# stm32f103_pin1.net
KiCad netlist of a schematic drawn in EAGLE
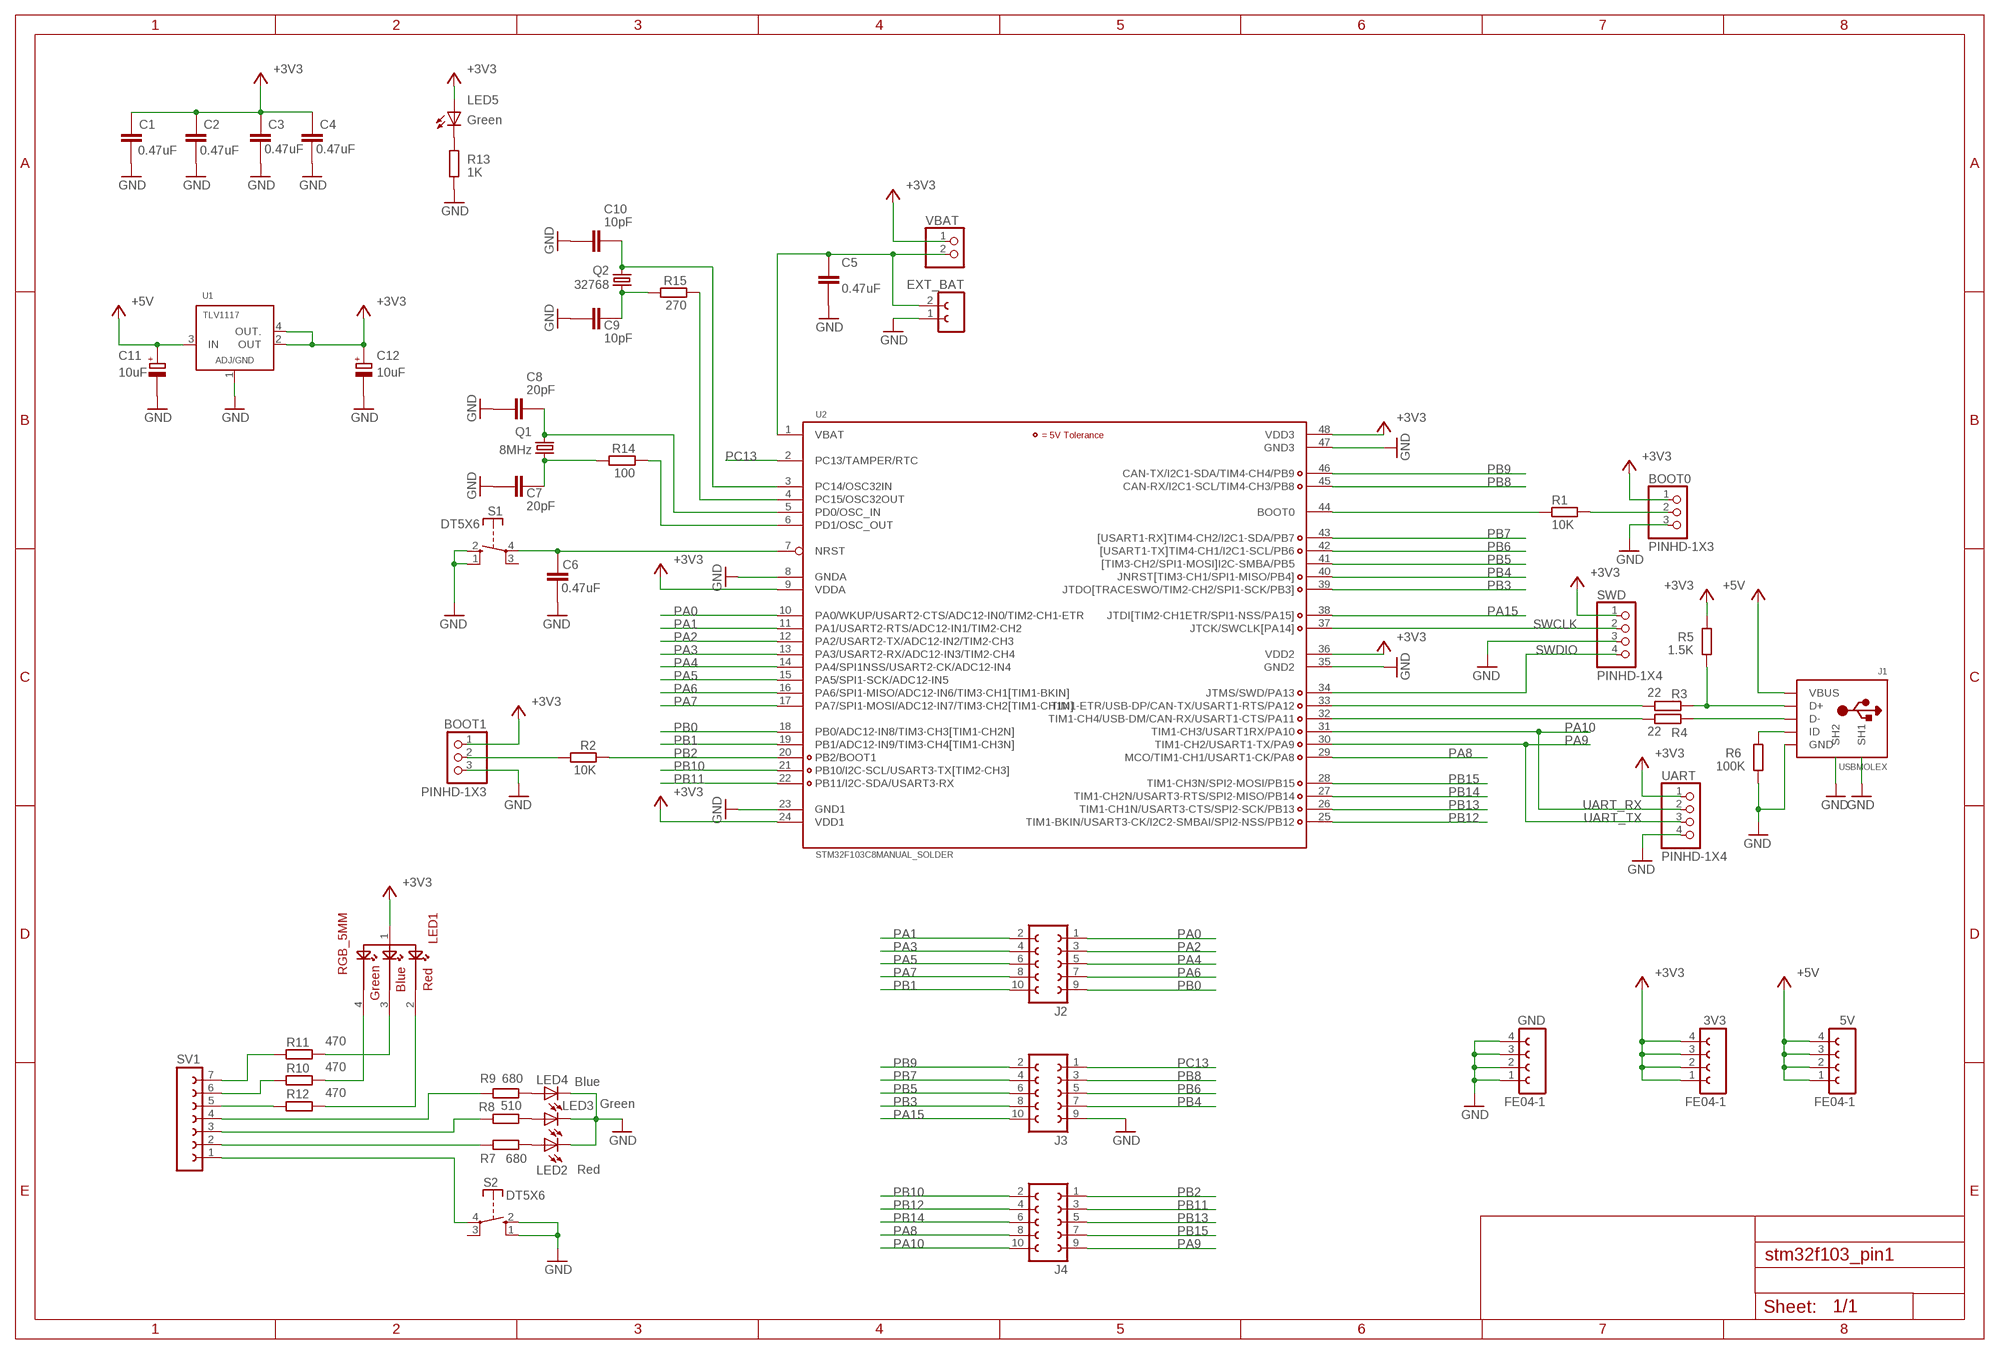
[diagram p0: schematic, sheet 1]

(export (version "E")
  (design (tool "Eeschema 10.0.6"))
  (components
    (comp (ref "3V3")
      (value "FE04-1")
      (footprint "eagle-import:FE04-1")
      (libsource (lib "eagle-import") (part "FE04-1"))
    )
    (comp (ref "5V")
      (value "FE04-1")
      (footprint "eagle-import:FE04-1")
      (libsource (lib "eagle-import") (part "FE04-1"))
    )
    (comp (ref "BOOT0")
      (value "PINHD-1X3")
      (footprint "eagle-import:1X03")
      (libsource (lib "eagle-import") (part "PINHD-1X3"))
    )
    (comp (ref "BOOT1")
      (value "PINHD-1X3")
      (footprint "eagle-import:1X03")
      (libsource (lib "eagle-import") (part "PINHD-1X3"))
    )
    (comp (ref "C1")
      (value "0.47uF")
      (footprint "eagle-import:CAPC2012X145AN")
      (libsource (lib "eagle-import") (part "CAPACITOR_0805"))
    )
    (comp (ref "C2")
      (value "0.47uF")
      (footprint "eagle-import:CAPC2012X145AN")
      (libsource (lib "eagle-import") (part "CAPACITOR_0805"))
    )
    (comp (ref "C3")
      (value "0.47uF")
      (footprint "eagle-import:CAPC2012X145AN")
      (libsource (lib "eagle-import") (part "CAPACITOR_0805"))
    )
    (comp (ref "C4")
      (value "0.47uF")
      (footprint "eagle-import:CAPC2012X145AN")
      (libsource (lib "eagle-import") (part "CAPACITOR_0805"))
    )
    (comp (ref "C5")
      (value "0.47uF")
      (footprint "eagle-import:CAPC2012X145AN")
      (libsource (lib "eagle-import") (part "CAPACITOR_0805"))
    )
    (comp (ref "C6")
      (value "0.47uF")
      (footprint "eagle-import:CAPC2012X145AN")
      (libsource (lib "eagle-import") (part "CAPACITOR_0805"))
    )
    (comp (ref "C7")
      (value "20pF")
      (footprint "eagle-import:CAPC2012X145AN")
      (libsource (lib "eagle-import") (part "CAPACITOR_0805"))
    )
    (comp (ref "C8")
      (value "20pF")
      (footprint "eagle-import:CAPC2012X145AN")
      (libsource (lib "eagle-import") (part "CAPACITOR_0805"))
    )
    (comp (ref "C9")
      (value "10pF")
      (footprint "eagle-import:CAPC2012X145AN")
      (libsource (lib "eagle-import") (part "CAPACITOR_0805"))
    )
    (comp (ref "C10")
      (value "10pF")
      (footprint "eagle-import:CAPC2012X145AN")
      (libsource (lib "eagle-import") (part "CAPACITOR_0805"))
    )
    (comp (ref "C11")
      (value "10uF")
      (footprint "eagle-import:CAPMP3216X180N")
      (libsource (lib "eagle-import") (part "POLARISED_A_CASE"))
    )
    (comp (ref "C12")
      (value "10uF")
      (footprint "eagle-import:CAPMP3216X180N")
      (libsource (lib "eagle-import") (part "POLARISED_A_CASE"))
    )
    (comp (ref "EXT_BAT")
      (value "FE02-1")
      (footprint "eagle-import:FE02-1")
      (libsource (lib "eagle-import") (part "FE02-1"))
    )
    (comp (ref "GND")
      (value "FE04-1")
      (footprint "eagle-import:FE04-1")
      (libsource (lib "eagle-import") (part "FE04-1"))
    )
    (comp (ref "J1")
      (value "USBMOLEX")
      (footprint "eagle-import:HW-MU-5F-20")
      (libsource (lib "eagle-import") (part "USBMOLEX"))
    )
    (comp (ref "J2")
      (value "FE05-2")
      (footprint "eagle-import:FE05-2")
      (fields (field (name "OC_FARNELL") "unknown") (field (name "OC_NEWARK") "unknown"))
      (libsource (lib "eagle-import") (part "FE05-2"))
    )
    (comp (ref "J3")
      (value "FE05-2")
      (footprint "eagle-import:FE05-2")
      (libsource (lib "eagle-import") (part "FE05-2"))
    )
    (comp (ref "J4")
      (value "FE05-2")
      (footprint "eagle-import:FE05-2")
      (fields (field (name "OC_FARNELL") "unknown") (field (name "OC_NEWARK") "unknown"))
      (libsource (lib "eagle-import") (part "FE05-2"))
    )
    (comp (ref "LED1")
      (value "RGB_5MM")
      (footprint "eagle-import:RGB_5MM")
      (libsource (lib "eagle-import") (part "RGB_5MM"))
    )
    (comp (ref "LED2")
      (value "Red")
      (footprint "eagle-import:CHIP-LED0805")
      (libsource (lib "eagle-import") (part "LEDCHIP-LED0805"))
    )
    (comp (ref "LED3")
      (value "Green")
      (footprint "eagle-import:CHIP-LED0805")
      (libsource (lib "eagle-import") (part "LEDCHIP-LED0805"))
    )
    (comp (ref "LED4")
      (value "Blue")
      (footprint "eagle-import:CHIP-LED0805")
      (libsource (lib "eagle-import") (part "LEDCHIP-LED0805"))
    )
    (comp (ref "LED5")
      (value "Green")
      (footprint "eagle-import:CHIP-LED0805")
      (libsource (lib "eagle-import") (part "LEDCHIP-LED0805"))
    )
    (comp (ref "Q1")
      (value "8MHz")
      (footprint "eagle-import:HC49_S")
      (libsource (lib "eagle-import") (part "CRYSTALHC49S"))
    )
    (comp (ref "Q2")
      (value "32768")
      (footprint "eagle-import:TC38H")
      (libsource (lib "eagle-import") (part "CRYSTALTC38H"))
    )
    (comp (ref "R1")
      (value "10K")
      (footprint "eagle-import:RESC2012X70N")
      (libsource (lib "eagle-import") (part "RESISTOR_0805"))
    )
    (comp (ref "R2")
      (value "10K")
      (footprint "eagle-import:RESC2012X70N")
      (libsource (lib "eagle-import") (part "RESISTOR_0805"))
    )
    (comp (ref "R3")
      (value "22")
      (footprint "eagle-import:RESC2012X70N")
      (libsource (lib "eagle-import") (part "RESISTOR_0805"))
    )
    (comp (ref "R4")
      (value "22")
      (footprint "eagle-import:RESC2012X70N")
      (libsource (lib "eagle-import") (part "RESISTOR_0805"))
    )
    (comp (ref "R5")
      (value "1.5K")
      (footprint "eagle-import:RESC2012X70N")
      (libsource (lib "eagle-import") (part "RESISTOR_0805"))
    )
    (comp (ref "R6")
      (value "100K")
      (footprint "eagle-import:RESC2012X70N")
      (libsource (lib "eagle-import") (part "RESISTOR_0805"))
    )
    (comp (ref "R7")
      (value "680")
      (footprint "eagle-import:RESC2012X70N")
      (libsource (lib "eagle-import") (part "RESISTOR_0805"))
    )
    (comp (ref "R8")
      (value "510")
      (footprint "eagle-import:RESC2012X70N")
      (libsource (lib "eagle-import") (part "RESISTOR_0805"))
    )
    (comp (ref "R9")
      (value "680")
      (footprint "eagle-import:RESC2012X70N")
      (libsource (lib "eagle-import") (part "RESISTOR_0805"))
    )
    (comp (ref "R10")
      (value "470")
      (footprint "eagle-import:RESC2012X70N")
      (libsource (lib "eagle-import") (part "RESISTOR_0805"))
    )
    (comp (ref "R11")
      (value "470")
      (footprint "eagle-import:RESC2012X70N")
      (libsource (lib "eagle-import") (part "RESISTOR_0805"))
    )
    (comp (ref "R12")
      (value "470")
      (footprint "eagle-import:RESC2012X70N")
      (libsource (lib "eagle-import") (part "RESISTOR_0805"))
    )
    (comp (ref "R13")
      (value "1K")
      (footprint "eagle-import:RESC2012X70N")
      (libsource (lib "eagle-import") (part "RESISTOR_0805"))
    )
    (comp (ref "R14")
      (value "100")
      (footprint "eagle-import:RESC2012X70N")
      (libsource (lib "eagle-import") (part "RESISTOR_0805"))
    )
    (comp (ref "R15")
      (value "270")
      (footprint "eagle-import:RESC2012X70N")
      (libsource (lib "eagle-import") (part "RESISTOR_0805"))
    )
    (comp (ref "S1")
      (value "DT5X6")
      (footprint "eagle-import:TACTILE-PTH")
      (libsource (lib "eagle-import") (part "DT5X6"))
    )
    (comp (ref "S2")
      (value "DT5X6")
      (footprint "eagle-import:TACTILE-PTH")
      (libsource (lib "eagle-import") (part "DT5X6"))
    )
    (comp (ref "SV1")
      (value "FE07-1")
      (footprint "eagle-import:FE07")
      (libsource (lib "eagle-import") (part "FE07-1"))
    )
    (comp (ref "SWD")
      (value "PINHD-1X4")
      (footprint "eagle-import:1X04")
      (libsource (lib "eagle-import") (part "PINHD-1X4"))
    )
    (comp (ref "U1")
      (value "TLV1117")
      (footprint "eagle-import:SOT223-4")
      (libsource (lib "eagle-import") (part "TLV1117"))
    )
    (comp (ref "U2")
      (value "STM32F103C8MANUAL_SOLDER")
      (footprint "eagle-import:LQFP48_IGORL")
      (libsource (lib "eagle-import") (part "STM32F103C8MANUAL_SOLDER"))
    )
    (comp (ref "UART")
      (value "PINHD-1X4")
      (footprint "eagle-import:1X04")
      (libsource (lib "eagle-import") (part "PINHD-1X4"))
    )
    (comp (ref "VBAT")
      (value "PINHD-1X2")
      (footprint "eagle-import:1X02")
      (libsource (lib "eagle-import") (part "PINHD-1X2"))
    )
  )
  (nets
    (net (code "1") (name "+3V3") (class "Default")
      (node (ref "3V3") (pin "1") (pinfunction "1_1") (pintype "passive"))
      (node (ref "3V3") (pin "2") (pinfunction "2_2") (pintype "passive"))
      (node (ref "3V3") (pin "3") (pinfunction "3_3") (pintype "passive"))
      (node (ref "3V3") (pin "4") (pinfunction "4_4") (pintype "passive"))
      (node (ref "BOOT0") (pin "1") (pinfunction "1_1") (pintype "passive"))
      (node (ref "BOOT1") (pin "1") (pinfunction "1_1") (pintype "passive"))
      (node (ref "C1") (pin "1") (pinfunction "1_1") (pintype "passive"))
      (node (ref "C12") (pin "+") (pinfunction "+_+") (pintype "passive"))
      (node (ref "C2") (pin "1") (pinfunction "1_1") (pintype "passive"))
      (node (ref "C3") (pin "1") (pinfunction "1_1") (pintype "passive"))
      (node (ref "C4") (pin "1") (pinfunction "1_1") (pintype "passive"))
      (node (ref "LED1") (pin "1") (pinfunction "1_1") (pintype "bidirectional"))
      (node (ref "LED5") (pin "A") (pinfunction "A_A") (pintype "passive"))
      (node (ref "R5") (pin "2") (pinfunction "2_2") (pintype "passive"))
      (node (ref "SWD") (pin "1") (pinfunction "1_1") (pintype "passive"))
      (node (ref "U1") (pin "2") (pinfunction "OUT_2") (pintype "power_in"))
      (node (ref "U1") (pin "4") (pinfunction "OUT._4") (pintype "power_in"))
      (node (ref "U2") (pin "24") (pinfunction "VDD1_24") (pintype "power_in"))
      (node (ref "U2") (pin "36") (pinfunction "VDD2_36") (pintype "power_in"))
      (node (ref "U2") (pin "48") (pinfunction "VDD3_48") (pintype "power_in"))
      (node (ref "U2") (pin "9") (pinfunction "VDDA_9") (pintype "power_in"))
      (node (ref "UART") (pin "1") (pinfunction "1_1") (pintype "passive"))
      (node (ref "VBAT") (pin "1") (pinfunction "1_1") (pintype "passive"))
    )
    (net (code "2") (name "+5V") (class "Default")
      (node (ref "5V") (pin "1") (pinfunction "1_1") (pintype "passive"))
      (node (ref "5V") (pin "2") (pinfunction "2_2") (pintype "passive"))
      (node (ref "5V") (pin "3") (pinfunction "3_3") (pintype "passive"))
      (node (ref "5V") (pin "4") (pinfunction "4_4") (pintype "passive"))
      (node (ref "C11") (pin "+") (pinfunction "+_+") (pintype "passive"))
      (node (ref "J1") (pin "VBUS") (pinfunction "VBUS_VBUS") (pintype "power_in"))
      (node (ref "U1") (pin "3") (pinfunction "IN_3") (pintype "power_in"))
    )
    (net (code "3") (name "/PA0") (class "Default")
      (node (ref "J2") (pin "1") (pinfunction "1_1") (pintype "passive"))
      (node (ref "U2") (pin "10") (pinfunction "PA0/WKUP/USART2-CTS/ADC12-IN0/TIM2-CH1-ETR_10") (pintype "bidirectional"))
    )
    (net (code "4") (name "/PA1") (class "Default")
      (node (ref "J2") (pin "2") (pinfunction "2_2") (pintype "passive"))
      (node (ref "U2") (pin "11") (pinfunction "PA1/USART2-RTS/ADC12-IN1/TIM2-CH2_11") (pintype "bidirectional"))
    )
    (net (code "5") (name "/PA2") (class "Default")
      (node (ref "J2") (pin "3") (pinfunction "3_3") (pintype "passive"))
      (node (ref "U2") (pin "12") (pinfunction "PA2/USART2-TX/ADC12-IN2/TIM2-CH3_12") (pintype "bidirectional"))
    )
    (net (code "6") (name "/PA3") (class "Default")
      (node (ref "J2") (pin "4") (pinfunction "4_4") (pintype "passive"))
      (node (ref "U2") (pin "13") (pinfunction "PA3/USART2-RX/ADC12-IN3/TIM2-CH4_13") (pintype "bidirectional"))
    )
    (net (code "7") (name "/PA4") (class "Default")
      (node (ref "J2") (pin "5") (pinfunction "5_5") (pintype "passive"))
      (node (ref "U2") (pin "14") (pinfunction "PA4/SPI1NSS/USART2-CK/ADC12-IN4_14") (pintype "bidirectional"))
    )
    (net (code "8") (name "/PA5") (class "Default")
      (node (ref "J2") (pin "6") (pinfunction "6_6") (pintype "passive"))
      (node (ref "U2") (pin "15") (pinfunction "PA5/SPI1-SCK/ADC12-IN5_15") (pintype "bidirectional"))
    )
    (net (code "9") (name "/PA6") (class "Default")
      (node (ref "J2") (pin "7") (pinfunction "7_7") (pintype "passive"))
      (node (ref "U2") (pin "16") (pinfunction "PA6/SPI1-MISO/ADC12-IN6/TIM3-CH1[TIM1-BKIN]_16") (pintype "bidirectional"))
    )
    (net (code "10") (name "/PA7") (class "Default")
      (node (ref "J2") (pin "8") (pinfunction "8_8") (pintype "passive"))
      (node (ref "U2") (pin "17") (pinfunction "PA7/SPI1-MOSI/ADC12-IN7/TIM3-CH2[TIM1-CH1N]_17") (pintype "bidirectional"))
    )
    (net (code "11") (name "/PA8") (class "Default")
      (node (ref "J4") (pin "8") (pinfunction "8_8") (pintype "passive"))
      (node (ref "U2") (pin "29") (pinfunction "MCO/TIM1-CH1/USART1-CK/PA8_29") (pintype "bidirectional"))
    )
    (net (code "12") (name "/PA9") (class "Default")
      (node (ref "J4") (pin "9") (pinfunction "9_9") (pintype "passive"))
      (node (ref "U2") (pin "30") (pinfunction "TIM1-CH2/USART1-TX/PA9_30") (pintype "bidirectional"))
      (node (ref "UART") (pin "3") (pinfunction "3_3") (pintype "passive"))
    )
    (net (code "13") (name "/PA10") (class "Default")
      (node (ref "J4") (pin "10") (pinfunction "10_10") (pintype "passive"))
      (node (ref "U2") (pin "31") (pinfunction "TIM1-CH3/USART1RX/PA10_31") (pintype "bidirectional"))
      (node (ref "UART") (pin "2") (pinfunction "2_2") (pintype "passive"))
    )
    (net (code "14") (name "/PA15") (class "Default")
      (node (ref "J3") (pin "10") (pinfunction "10_10") (pintype "passive"))
      (node (ref "U2") (pin "38") (pinfunction "JTDI[TIM2-CH1ETR/SPI1-NSS/PA15]_38") (pintype "bidirectional"))
    )
    (net (code "15") (name "/PB0") (class "Default")
      (node (ref "J2") (pin "9") (pinfunction "9_9") (pintype "passive"))
      (node (ref "U2") (pin "18") (pinfunction "PB0/ADC12-IN8/TIM3-CH3[TIM1-CH2N]_18") (pintype "bidirectional"))
    )
    (net (code "16") (name "/PB1") (class "Default")
      (node (ref "J2") (pin "10") (pinfunction "10_10") (pintype "passive"))
      (node (ref "U2") (pin "19") (pinfunction "PB1/ADC12-IN9/TIM3-CH4[TIM1-CH3N]_19") (pintype "bidirectional"))
    )
    (net (code "17") (name "/PB2") (class "Default")
      (node (ref "J4") (pin "1") (pinfunction "1_1") (pintype "passive"))
      (node (ref "R2") (pin "1") (pinfunction "1_1") (pintype "passive"))
      (node (ref "U2") (pin "20") (pinfunction "PB2/BOOT1_20") (pintype "bidirectional"))
    )
    (net (code "18") (name "/PB3") (class "Default")
      (node (ref "J3") (pin "8") (pinfunction "8_8") (pintype "passive"))
      (node (ref "U2") (pin "39") (pinfunction "JTDO[TRACESWO/TIM2-CH2/SPI1-SCK/PB3]_39") (pintype "bidirectional"))
    )
    (net (code "19") (name "/PB4") (class "Default")
      (node (ref "J3") (pin "7") (pinfunction "7_7") (pintype "passive"))
      (node (ref "U2") (pin "40") (pinfunction "JNRST[TIM3-CH1/SPI1-MISO/PB4]_40") (pintype "bidirectional"))
    )
    (net (code "20") (name "/PB5") (class "Default")
      (node (ref "J3") (pin "6") (pinfunction "6_6") (pintype "passive"))
      (node (ref "U2") (pin "41") (pinfunction "[TIM3-CH2/SPI1-MOSI]I2C-SMBA/PB5_41") (pintype "bidirectional"))
    )
    (net (code "21") (name "/PB6") (class "Default")
      (node (ref "J3") (pin "5") (pinfunction "5_5") (pintype "passive"))
      (node (ref "U2") (pin "42") (pinfunction "[USART1-TX]TIM4-CH1/I2C1-SCL/PB6_42") (pintype "bidirectional"))
    )
    (net (code "22") (name "/PB7") (class "Default")
      (node (ref "J3") (pin "4") (pinfunction "4_4") (pintype "passive"))
      (node (ref "U2") (pin "43") (pinfunction "[USART1-RX]TIM4-CH2/I2C1-SDA/PB7_43") (pintype "bidirectional"))
    )
    (net (code "23") (name "/PB8") (class "Default")
      (node (ref "J3") (pin "3") (pinfunction "3_3") (pintype "passive"))
      (node (ref "U2") (pin "45") (pinfunction "CAN-RX/I2C1-SCL/TIM4-CH3/PB8_45") (pintype "bidirectional"))
    )
    (net (code "24") (name "/PB9") (class "Default")
      (node (ref "J3") (pin "2") (pinfunction "2_2") (pintype "passive"))
      (node (ref "U2") (pin "46") (pinfunction "CAN-TX/I2C1-SDA/TIM4-CH4/PB9_46") (pintype "bidirectional"))
    )
    (net (code "25") (name "/PB10") (class "Default")
      (node (ref "J4") (pin "2") (pinfunction "2_2") (pintype "passive"))
      (node (ref "U2") (pin "21") (pinfunction "PB10/I2C-SCL/USART3-TX[TIM2-CH3]_21") (pintype "bidirectional"))
    )
    (net (code "26") (name "/PB11") (class "Default")
      (node (ref "J4") (pin "3") (pinfunction "3_3") (pintype "passive"))
      (node (ref "U2") (pin "22") (pinfunction "PB11/I2C-SDA/USART3-RX_22") (pintype "bidirectional"))
    )
    (net (code "27") (name "/PB12") (class "Default")
      (node (ref "J4") (pin "4") (pinfunction "4_4") (pintype "passive"))
      (node (ref "U2") (pin "25") (pinfunction "TIM1-BKIN/USART3-CK/I2C2-SMBAI/SPI2-NSS/PB12_25") (pintype "bidirectional"))
    )
    (net (code "28") (name "/PB13") (class "Default")
      (node (ref "J4") (pin "5") (pinfunction "5_5") (pintype "passive"))
      (node (ref "U2") (pin "26") (pinfunction "TIM1-CH1N/USART3-CTS/SPI2-SCK/PB13_26") (pintype "bidirectional"))
    )
    (net (code "29") (name "/PB14") (class "Default")
      (node (ref "J4") (pin "6") (pinfunction "6_6") (pintype "passive"))
      (node (ref "U2") (pin "27") (pinfunction "TIM1-CH2N/USART3-RTS/SPI2-MISO/PB14_27") (pintype "bidirectional"))
    )
    (net (code "30") (name "/PB15") (class "Default")
      (node (ref "J4") (pin "7") (pinfunction "7_7") (pintype "passive"))
      (node (ref "U2") (pin "28") (pinfunction "TIM1-CH3N/SPI2-MOSI/PB15_28") (pintype "bidirectional"))
    )
    (net (code "31") (name "/PC13") (class "Default")
      (node (ref "J3") (pin "1") (pinfunction "1_1") (pintype "passive"))
      (node (ref "U2") (pin "2") (pinfunction "PC13/TAMPER/RTC_2") (pintype "bidirectional"))
    )
    (net (code "32") (name "GND") (class "Default")
      (node (ref "BOOT0") (pin "3") (pinfunction "3_3") (pintype "passive"))
      (node (ref "BOOT1") (pin "3") (pinfunction "3_3") (pintype "passive"))
      (node (ref "C1") (pin "2") (pinfunction "2_2") (pintype "passive"))
      (node (ref "C10") (pin "2") (pinfunction "2_2") (pintype "passive"))
      (node (ref "C11") (pin "-") (pinfunction "-_-") (pintype "passive"))
      (node (ref "C12") (pin "-") (pinfunction "-_-") (pintype "passive"))
      (node (ref "C2") (pin "2") (pinfunction "2_2") (pintype "passive"))
      (node (ref "C3") (pin "2") (pinfunction "2_2") (pintype "passive"))
      (node (ref "C4") (pin "2") (pinfunction "2_2") (pintype "passive"))
      (node (ref "C5") (pin "2") (pinfunction "2_2") (pintype "passive"))
      (node (ref "C6") (pin "2") (pinfunction "2_2") (pintype "passive"))
      (node (ref "C7") (pin "2") (pinfunction "2_2") (pintype "passive"))
      (node (ref "C8") (pin "2") (pinfunction "2_2") (pintype "passive"))
      (node (ref "C9") (pin "2") (pinfunction "2_2") (pintype "passive"))
      (node (ref "EXT_BAT") (pin "1") (pinfunction "1_1") (pintype "passive"))
      (node (ref "GND") (pin "1") (pinfunction "1_1") (pintype "passive"))
      (node (ref "GND") (pin "2") (pinfunction "2_2") (pintype "passive"))
      (node (ref "GND") (pin "3") (pinfunction "3_3") (pintype "passive"))
      (node (ref "GND") (pin "4") (pinfunction "4_4") (pintype "passive"))
      (node (ref "J1") (pin "GND") (pinfunction "GND_GND") (pintype "power_in"))
      (node (ref "J1") (pin "SH1") (pinfunction "SH1_SH1") (pintype "power_in"))
      (node (ref "J1") (pin "SH2") (pinfunction "SH2_SH2") (pintype "power_in"))
      (node (ref "J3") (pin "9") (pinfunction "9_9") (pintype "passive"))
      (node (ref "LED2") (pin "C") (pinfunction "C_C") (pintype "passive"))
      (node (ref "LED3") (pin "C") (pinfunction "C_C") (pintype "passive"))
      (node (ref "LED4") (pin "C") (pinfunction "C_C") (pintype "passive"))
      (node (ref "R13") (pin "1") (pinfunction "1_1") (pintype "passive"))
      (node (ref "R6") (pin "2") (pinfunction "2_2") (pintype "passive"))
      (node (ref "S1") (pin "1") (pinfunction "S_1") (pintype "passive"))
      (node (ref "S1") (pin "2") (pinfunction "S_2") (pintype "passive"))
      (node (ref "S2") (pin "1") (pinfunction "S_1") (pintype "passive"))
      (node (ref "S2") (pin "2") (pinfunction "S_2") (pintype "passive"))
      (node (ref "SWD") (pin "3") (pinfunction "3_3") (pintype "passive"))
      (node (ref "U1") (pin "1") (pinfunction "ADJ/GND_1") (pintype "bidirectional"))
      (node (ref "U2") (pin "23") (pinfunction "GND1_23") (pintype "power_in"))
      (node (ref "U2") (pin "35") (pinfunction "GND2_35") (pintype "power_in"))
      (node (ref "U2") (pin "47") (pinfunction "GND3_47") (pintype "power_in"))
      (node (ref "U2") (pin "8") (pinfunction "GNDA_8") (pintype "power_in"))
      (node (ref "UART") (pin "4") (pinfunction "4_4") (pintype "passive"))
    )
    (net (code "33") (name "Net-(BOOT0-Pad2)") (class "Default")
      (node (ref "BOOT0") (pin "2") (pinfunction "2_2") (pintype "passive"))
      (node (ref "R1") (pin "2") (pinfunction "2_2") (pintype "passive"))
    )
    (net (code "34") (name "Net-(BOOT1-Pad2)") (class "Default")
      (node (ref "BOOT1") (pin "2") (pinfunction "2_2") (pintype "passive"))
      (node (ref "R2") (pin "2") (pinfunction "2_2") (pintype "passive"))
    )
    (net (code "35") (name "Net-(C7-Pad1)") (class "Default")
      (node (ref "C7") (pin "1") (pinfunction "1_1") (pintype "passive"))
      (node (ref "Q1") (pin "1") (pinfunction "1_1") (pintype "passive"))
      (node (ref "R14") (pin "2") (pinfunction "2_2") (pintype "passive"))
    )
    (net (code "36") (name "Net-(C9-Pad1)") (class "Default")
      (node (ref "C9") (pin "1") (pinfunction "1_1") (pintype "passive"))
      (node (ref "Q2") (pin "1") (pinfunction "1_1") (pintype "passive"))
      (node (ref "R15") (pin "2") (pinfunction "2_2") (pintype "passive"))
    )
    (net (code "37") (name "Net-(J1-PadD+)") (class "Default")
      (node (ref "J1") (pin "D+") (pinfunction "D+_D+") (pintype "bidirectional"))
      (node (ref "R3") (pin "1") (pinfunction "1_1") (pintype "passive"))
      (node (ref "R5") (pin "1") (pinfunction "1_1") (pintype "passive"))
    )
    (net (code "38") (name "Net-(J1-PadD-)") (class "Default")
      (node (ref "J1") (pin "D-") (pinfunction "D-_D-") (pintype "bidirectional"))
      (node (ref "R4") (pin "1") (pinfunction "1_1") (pintype "passive"))
    )
    (net (code "39") (name "Net-(J1-PadID)") (class "Default")
      (node (ref "J1") (pin "ID") (pinfunction "ID_ID") (pintype "bidirectional"))
      (node (ref "R6") (pin "1") (pinfunction "1_1") (pintype "passive"))
    )
    (net (code "40") (name "Net-(LED1-Pad2)") (class "Default")
      (node (ref "LED1") (pin "2") (pinfunction "2_2") (pintype "bidirectional"))
      (node (ref "R12") (pin "2") (pinfunction "2_2") (pintype "passive"))
    )
    (net (code "41") (name "Net-(LED1-Pad3)") (class "Default")
      (node (ref "LED1") (pin "3") (pinfunction "3_3") (pintype "bidirectional"))
      (node (ref "R11") (pin "2") (pinfunction "2_2") (pintype "passive"))
    )
    (net (code "42") (name "Net-(LED1-Pad4)") (class "Default")
      (node (ref "LED1") (pin "4") (pinfunction "4_4") (pintype "bidirectional"))
      (node (ref "R10") (pin "2") (pinfunction "2_2") (pintype "passive"))
    )
    (net (code "43") (name "Net-(LED2-PadA)") (class "Default")
      (node (ref "LED2") (pin "A") (pinfunction "A_A") (pintype "passive"))
      (node (ref "R7") (pin "2") (pinfunction "2_2") (pintype "passive"))
    )
    (net (code "44") (name "Net-(LED3-PadA)") (class "Default")
      (node (ref "LED3") (pin "A") (pinfunction "A_A") (pintype "passive"))
      (node (ref "R8") (pin "2") (pinfunction "2_2") (pintype "passive"))
    )
    (net (code "45") (name "Net-(LED4-PadA)") (class "Default")
      (node (ref "LED4") (pin "A") (pinfunction "A_A") (pintype "passive"))
      (node (ref "R9") (pin "2") (pinfunction "2_2") (pintype "passive"))
    )
    (net (code "46") (name "Net-(LED5-PadC)") (class "Default")
      (node (ref "LED5") (pin "C") (pinfunction "C_C") (pintype "passive"))
      (node (ref "R13") (pin "2") (pinfunction "2_2") (pintype "passive"))
    )
    (net (code "47") (name "Net-(R7-Pad1)") (class "Default")
      (node (ref "R7") (pin "1") (pinfunction "1_1") (pintype "passive"))
      (node (ref "SV1") (pin "2") (pinfunction "2_2") (pintype "passive"))
    )
    (net (code "48") (name "Net-(R8-Pad1)") (class "Default")
      (node (ref "R8") (pin "1") (pinfunction "1_1") (pintype "passive"))
      (node (ref "SV1") (pin "3") (pinfunction "3_3") (pintype "passive"))
    )
    (net (code "49") (name "Net-(R9-Pad1)") (class "Default")
      (node (ref "R9") (pin "1") (pinfunction "1_1") (pintype "passive"))
      (node (ref "SV1") (pin "4") (pinfunction "4_4") (pintype "passive"))
    )
    (net (code "50") (name "Net-(R10-Pad1)") (class "Default")
      (node (ref "R10") (pin "1") (pinfunction "1_1") (pintype "passive"))
      (node (ref "SV1") (pin "6") (pinfunction "6_6") (pintype "passive"))
    )
    (net (code "51") (name "Net-(R11-Pad1)") (class "Default")
      (node (ref "R11") (pin "1") (pinfunction "1_1") (pintype "passive"))
      (node (ref "SV1") (pin "7") (pinfunction "7_7") (pintype "passive"))
    )
    (net (code "52") (name "Net-(R12-Pad1)") (class "Default")
      (node (ref "R12") (pin "1") (pinfunction "1_1") (pintype "passive"))
      (node (ref "SV1") (pin "5") (pinfunction "5_5") (pintype "passive"))
    )
    (net (code "53") (name "Net-(S2-P-Pad4)") (class "Default")
      (node (ref "S2") (pin "4") (pinfunction "P_4") (pintype "passive"))
      (node (ref "SV1") (pin "1") (pinfunction "1_1") (pintype "passive"))
    )
    (net (code "54") (name "Net-(U2-BOOT0)") (class "Default")
      (node (ref "R1") (pin "1") (pinfunction "1_1") (pintype "passive"))
      (node (ref "U2") (pin "44") (pinfunction "BOOT0_44") (pintype "bidirectional"))
    )
    (net (code "55") (name "Net-(U2-JTCK{slash}SWCLK[PA14])") (class "Default")
      (node (ref "SWD") (pin "2") (pinfunction "2_2") (pintype "passive"))
      (node (ref "U2") (pin "37") (pinfunction "JTCK/SWCLK[PA14]_37") (pintype "bidirectional"))
    )
    (net (code "56") (name "Net-(U2-JTMS{slash}SWD{slash}PA13)") (class "Default")
      (node (ref "SWD") (pin "4") (pinfunction "4_4") (pintype "passive"))
      (node (ref "U2") (pin "34") (pinfunction "JTMS/SWD/PA13_34") (pintype "bidirectional"))
    )
    (net (code "57") (name "Net-(U2-NRST)") (class "Default")
      (node (ref "C6") (pin "1") (pinfunction "1_1") (pintype "passive"))
      (node (ref "S1") (pin "4") (pinfunction "P_4") (pintype "passive"))
      (node (ref "U2") (pin "7") (pinfunction "NRST_7") (pintype "bidirectional"))
    )
    (net (code "58") (name "Net-(U2-PC14{slash}OSC32IN)") (class "Default")
      (node (ref "C10") (pin "1") (pinfunction "1_1") (pintype "passive"))
      (node (ref "Q2") (pin "2") (pinfunction "2_2") (pintype "passive"))
      (node (ref "U2") (pin "3") (pinfunction "PC14/OSC32IN_3") (pintype "bidirectional"))
    )
    (net (code "59") (name "Net-(U2-PC15{slash}OSC32OUT)") (class "Default")
      (node (ref "R15") (pin "1") (pinfunction "1_1") (pintype "passive"))
      (node (ref "U2") (pin "4") (pinfunction "PC15/OSC32OUT_4") (pintype "bidirectional"))
    )
    (net (code "60") (name "Net-(U2-PD0{slash}OSC_IN)") (class "Default")
      (node (ref "C8") (pin "1") (pinfunction "1_1") (pintype "passive"))
      (node (ref "Q1") (pin "2") (pinfunction "2_2") (pintype "passive"))
      (node (ref "U2") (pin "5") (pinfunction "PD0/OSC_IN_5") (pintype "bidirectional"))
    )
    (net (code "61") (name "Net-(U2-PD1{slash}OSC_OUT)") (class "Default")
      (node (ref "R14") (pin "1") (pinfunction "1_1") (pintype "passive"))
      (node (ref "U2") (pin "6") (pinfunction "PD1/OSC_OUT_6") (pintype "bidirectional"))
    )
    (net (code "62") (name "Net-(U2-TIM1-CH4{slash}USB-DM{slash}CAN-RX{slash}USART1-CTS{slash}PA11)") (class "Default")
      (node (ref "R4") (pin "2") (pinfunction "2_2") (pintype "passive"))
      (node (ref "U2") (pin "32") (pinfunction "TIM1-CH4/USB-DM/CAN-RX/USART1-CTS/PA11_32") (pintype "bidirectional"))
    )
    (net (code "63") (name "Net-(U2-TIM1-ETR{slash}USB-DP{slash}CAN-TX{slash}USART1-RTS{slash}PA12)") (class "Default")
      (node (ref "R3") (pin "2") (pinfunction "2_2") (pintype "passive"))
      (node (ref "U2") (pin "33") (pinfunction "TIM1-ETR/USB-DP/CAN-TX/USART1-RTS/PA12_33") (pintype "bidirectional"))
    )
    (net (code "64") (name "Net-(U2-VBAT)") (class "Default")
      (node (ref "C5") (pin "1") (pinfunction "1_1") (pintype "passive"))
      (node (ref "EXT_BAT") (pin "2") (pinfunction "2_2") (pintype "passive"))
      (node (ref "U2") (pin "1") (pinfunction "VBAT_1") (pintype "power_in"))
      (node (ref "VBAT") (pin "2") (pinfunction "2_2") (pintype "passive"))
    )
    (net (code "65") (name "unconnected-(S1-P-Pad3)") (class "Default")
      (node (ref "S1") (pin "3") (pinfunction "P_3") (pintype "passive"))
    )
    (net (code "66") (name "unconnected-(S2-P-Pad3)") (class "Default")
      (node (ref "S2") (pin "3") (pinfunction "P_3") (pintype "passive"))
    )
  )
)
